# Headphone-Amplifier-ClassAB-long.net
KiCad netlist of a schematic drawn in EAGLE
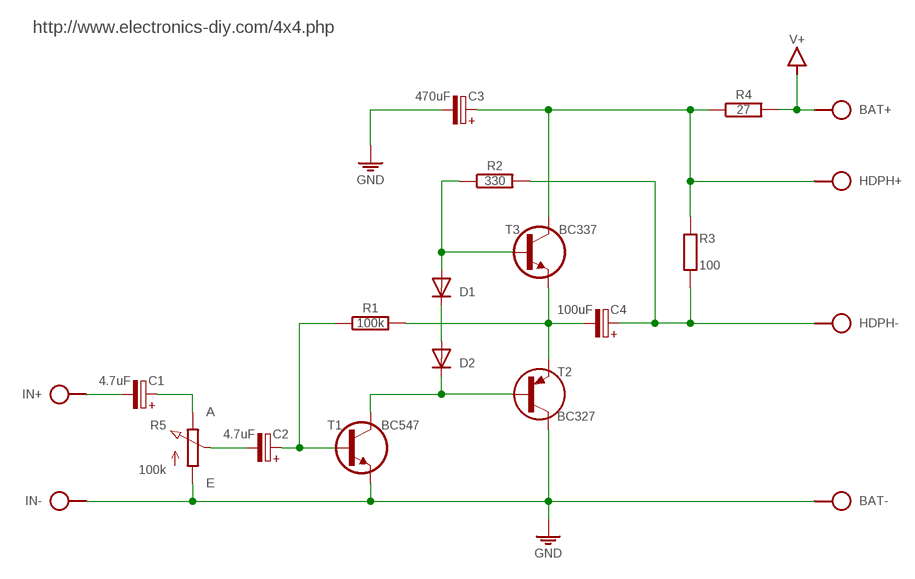
[diagram p0: schematic, sheet 1]

(export (version "E")
  (design (tool "Eeschema 10.0.6"))
  (components
    (comp (ref "BAT")
      (value "SPAD+-+-")
      (footprint "eagle-import:SPAD+-")
      (libsource (lib "eagle-import") (part "SPAD+-+-"))
    )
    (comp (ref "C1")
      (value "4.7uF")
      (footprint "eagle-import:E2,5-4")
      (libsource (lib "eagle-import") (part "CPOL-HE2,5-4"))
    )
    (comp (ref "C2")
      (value "4.7uF")
      (footprint "eagle-import:E2,5-4")
      (libsource (lib "eagle-import") (part "CPOL-HE2,5-4"))
    )
    (comp (ref "C3")
      (value "470uF")
      (footprint "eagle-import:E5-5_V")
      (libsource (lib "eagle-import") (part "CPOL-HE5-5/V"))
    )
    (comp (ref "C4")
      (value "100uF")
      (footprint "eagle-import:E5-4")
      (libsource (lib "eagle-import") (part "CPOL-HE5-4"))
    )
    (comp (ref "D1")
      (value "1N414834-5V")
      (footprint "eagle-import:DO34-5V")
      (libsource (lib "eagle-import") (part "1N414834-5V"))
    )
    (comp (ref "D2")
      (value "1N414834-5V")
      (footprint "eagle-import:DO34-5V")
      (libsource (lib "eagle-import") (part "1N414834-5V"))
    )
    (comp (ref "HDPH")
      (value "SPAD+--+")
      (footprint "eagle-import:SPAD-+")
      (libsource (lib "eagle-import") (part "SPAD+--+"))
    )
    (comp (ref "IN")
      (value "SPAD+--+")
      (footprint "eagle-import:SPAD-+")
      (libsource (lib "eagle-import") (part "SPAD+--+"))
    )
    (comp (ref "R1")
      (value "100k")
      (footprint "eagle-import:0202_7")
      (libsource (lib "eagle-import") (part "R-H0202/7"))
    )
    (comp (ref "R2")
      (value "330")
      (footprint "eagle-import:0202_7")
      (libsource (lib "eagle-import") (part "R-H0202/7"))
    )
    (comp (ref "R3")
      (value "100")
      (footprint "eagle-import:0202_7")
      (libsource (lib "eagle-import") (part "R0202/7"))
    )
    (comp (ref "R4")
      (value "27")
      (footprint "eagle-import:0204_2V")
      (libsource (lib "eagle-import") (part "R-H0204/2V"))
    )
    (comp (ref "R5")
      (value "100k")
      (footprint "eagle-import:CONN-3P")
      (libsource (lib "eagle-import") (part "POT-3P"))
    )
    (comp (ref "T1")
      (value "BC547")
      (footprint "eagle-import:TO92-CBE")
      (libsource (lib "eagle-import") (part "BC547CBE"))
    )
    (comp (ref "T2")
      (value "BC327")
      (footprint "eagle-import:TO92")
      (libsource (lib "eagle-import") (part "BC327"))
    )
    (comp (ref "T3")
      (value "BC337")
      (footprint "eagle-import:TO92-CBE")
      (libsource (lib "eagle-import") (part "BC337CBE"))
    )
  )
  (nets
    (net (code "1") (name "GND") (class "Default")
      (node (ref "BAT") (pin "1") (pinfunction "P$1_1") (pintype "passive"))
      (node (ref "C3") (pin "-") (pinfunction "-_-") (pintype "passive"))
      (node (ref "IN") (pin "1") (pinfunction "P$1_1") (pintype "passive"))
      (node (ref "R5") (pin "1") (pinfunction "A_1") (pintype "passive"))
      (node (ref "T1") (pin "E") (pinfunction "E_E") (pintype "passive"))
      (node (ref "T2") (pin "1") (pinfunction "C_1") (pintype "passive"))
    )
    (net (code "2") (name "Net-(C2-Pad+)") (class "Default")
      (node (ref "C2") (pin "+") (pinfunction "+_+") (pintype "passive"))
      (node (ref "R1") (pin "1") (pinfunction "1_1") (pintype "passive"))
      (node (ref "T1") (pin "B") (pinfunction "B_B") (pintype "passive"))
    )
    (net (code "3") (name "Net-(D1-PadA)") (class "Default")
      (node (ref "D1") (pin "A") (pinfunction "A_A") (pintype "passive"))
      (node (ref "R2") (pin "1") (pinfunction "1_1") (pintype "passive"))
      (node (ref "T3") (pin "B") (pinfunction "B_B") (pintype "passive"))
    )
    (net (code "4") (name "Net-(D1-PadC)") (class "Default")
      (node (ref "D1") (pin "C") (pinfunction "C_C") (pintype "passive"))
      (node (ref "D2") (pin "A") (pinfunction "A_A") (pintype "passive"))
    )
    (net (code "5") (name "Net-(HDPHA-P$1)") (class "Default")
      (node (ref "C3") (pin "+") (pinfunction "+_+") (pintype "passive"))
      (node (ref "HDPH") (pin "2") (pinfunction "P$1_2") (pintype "passive"))
      (node (ref "R3") (pin "1") (pinfunction "1_1") (pintype "passive"))
      (node (ref "R4") (pin "1") (pinfunction "1_1") (pintype "passive"))
      (node (ref "T3") (pin "C") (pinfunction "C_C") (pintype "passive"))
    )
    (net (code "6") (name "Net-(HDPHB-P$1)") (class "Default")
      (node (ref "C4") (pin "+") (pinfunction "+_+") (pintype "passive"))
      (node (ref "HDPH") (pin "1") (pinfunction "P$1_1") (pintype "passive"))
      (node (ref "R2") (pin "2") (pinfunction "2_2") (pintype "passive"))
      (node (ref "R3") (pin "2") (pinfunction "2_2") (pintype "passive"))
    )
    (net (code "7") (name "Net-(INA-P$1)") (class "Default")
      (node (ref "C1") (pin "-") (pinfunction "-_-") (pintype "passive"))
      (node (ref "IN") (pin "2") (pinfunction "P$1_2") (pintype "passive"))
    )
    (net (code "8") (name "Net-(R5-E)") (class "Default")
      (node (ref "C1") (pin "+") (pinfunction "+_+") (pintype "passive"))
      (node (ref "R5") (pin "3") (pinfunction "E_3") (pintype "passive"))
    )
    (net (code "9") (name "Net-(R5-S)") (class "Default")
      (node (ref "C2") (pin "-") (pinfunction "-_-") (pintype "passive"))
      (node (ref "R5") (pin "2") (pinfunction "S_2") (pintype "passive"))
    )
    (net (code "10") (name "Net-(T2-B)") (class "Default")
      (node (ref "D2") (pin "C") (pinfunction "C_C") (pintype "passive"))
      (node (ref "T1") (pin "C") (pinfunction "C_C") (pintype "passive"))
      (node (ref "T2") (pin "2") (pinfunction "B_2") (pintype "passive"))
    )
    (net (code "11") (name "Net-(T2-E)") (class "Default")
      (node (ref "C4") (pin "-") (pinfunction "-_-") (pintype "passive"))
      (node (ref "R1") (pin "2") (pinfunction "2_2") (pintype "passive"))
      (node (ref "T2") (pin "3") (pinfunction "E_3") (pintype "passive"))
      (node (ref "T3") (pin "E") (pinfunction "E_E") (pintype "passive"))
    )
    (net (code "12") (name "V+") (class "Default")
      (node (ref "BAT") (pin "2") (pinfunction "P$1_2") (pintype "passive"))
      (node (ref "R4") (pin "2") (pinfunction "2_2") (pintype "passive"))
    )
  )
)
